# Protoboard.net
KiCad netlist of a schematic drawn in EAGLE
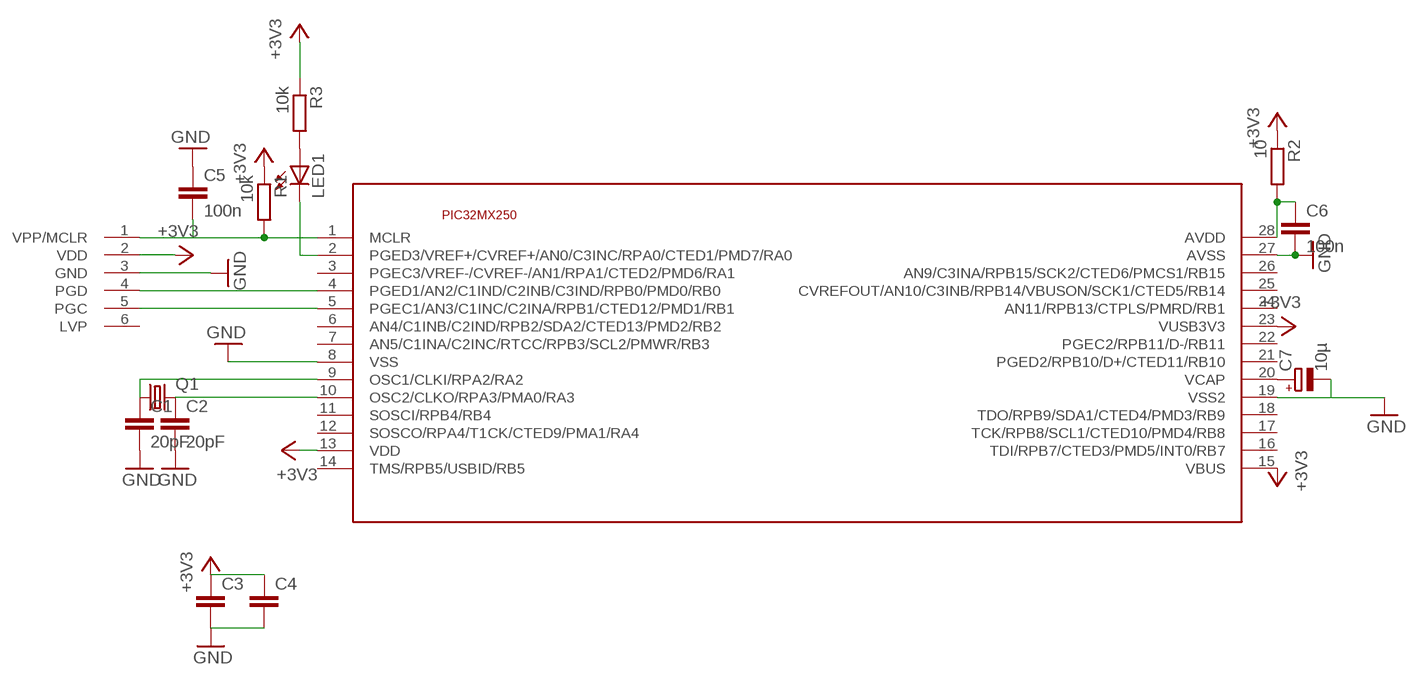
[diagram p0: schematic, sheet 1]

(export (version "E")
  (design (tool "Eeschema 10.0.6"))
  (components
    (comp (ref "C1")
      (value "20pF")
      (footprint "eagle-import:C050-024X044")
      (libsource (lib "eagle-import") (part "C-EU050-024X044"))
    )
    (comp (ref "C2")
      (value "20pF")
      (footprint "eagle-import:C050-024X044")
      (libsource (lib "eagle-import") (part "C-EU050-024X044"))
    )
    (comp (ref "C3")
      (value "C-EU050-024X044")
      (footprint "eagle-import:C050-024X044")
      (libsource (lib "eagle-import") (part "C-EU050-024X044"))
    )
    (comp (ref "C4")
      (value "C-EU050-024X044")
      (footprint "eagle-import:C050-024X044")
      (libsource (lib "eagle-import") (part "C-EU050-024X044"))
    )
    (comp (ref "C5")
      (value "100n")
      (footprint "eagle-import:C050-024X044")
      (libsource (lib "eagle-import") (part "C-EU050-024X044"))
    )
    (comp (ref "C6")
      (value "100n")
      (footprint "eagle-import:C050-024X044")
      (libsource (lib "eagle-import") (part "C-EU050-024X044"))
    )
    (comp (ref "C7")
      (value "10µ")
      (footprint "eagle-import:B45181B")
      (libsource (lib "eagle-import") (part "CPOL-EUB45181B"))
    )
    (comp (ref "LED1")
      (value "LED5MM")
      (footprint "eagle-import:LED5MM")
      (libsource (lib "eagle-import") (part "LED5MM"))
    )
    (comp (ref "Q1")
      (value "CRYSTALTC26V")
      (footprint "eagle-import:TC26V")
      (libsource (lib "eagle-import") (part "CRYSTALTC26V"))
    )
    (comp (ref "R1")
      (value "10k")
      (footprint "eagle-import:0207_10")
      (libsource (lib "eagle-import") (part "R-EU_0207/10"))
    )
    (comp (ref "R2")
      (value "10")
      (footprint "eagle-import:0207_10")
      (libsource (lib "eagle-import") (part "R-EU_0207/10"))
    )
    (comp (ref "R3")
      (value "10k")
      (footprint "eagle-import:0207_10")
      (libsource (lib "eagle-import") (part "R-EU_0207/10"))
    )
    (comp (ref "U$2")
      (value "ICSP-6_6P")
      (footprint "eagle-import:1X06-CLEANBIG")
      (libsource (lib "eagle-import") (part "ICSP-6_6P"))
    )
    (comp (ref "U$3")
      (value "PIC32MX2XXSOIC")
      (footprint "eagle-import:SOIC28")
      (libsource (lib "eagle-import") (part "PIC32MX2XXSOIC"))
    )
  )
  (nets
    (net (code "1") (name "+3V3") (class "Default")
      (node (ref "C3") (pin "1") (pinfunction "1_1") (pintype "passive"))
      (node (ref "C4") (pin "1") (pinfunction "1_1") (pintype "passive"))
      (node (ref "R1") (pin "1") (pinfunction "1_1") (pintype "passive"))
      (node (ref "R2") (pin "1") (pinfunction "1_1") (pintype "passive"))
      (node (ref "R3") (pin "1") (pinfunction "1_1") (pintype "passive"))
      (node (ref "U$2") (pin "2") (pinfunction "VDD_2") (pintype "bidirectional"))
      (node (ref "U$3") (pin "13") (pinfunction "VDD_13") (pintype "power_in"))
      (node (ref "U$3") (pin "15") (pinfunction "VBUS_15") (pintype "bidirectional"))
      (node (ref "U$3") (pin "23") (pinfunction "VUSB3V3_23") (pintype "bidirectional"))
    )
    (net (code "2") (name "GND") (class "Default")
      (node (ref "C1") (pin "2") (pinfunction "2_2") (pintype "passive"))
      (node (ref "C2") (pin "2") (pinfunction "2_2") (pintype "passive"))
      (node (ref "C3") (pin "2") (pinfunction "2_2") (pintype "passive"))
      (node (ref "C4") (pin "2") (pinfunction "2_2") (pintype "passive"))
      (node (ref "C5") (pin "1") (pinfunction "1_1") (pintype "passive"))
      (node (ref "C6") (pin "2") (pinfunction "2_2") (pintype "passive"))
      (node (ref "C7") (pin "-") (pinfunction "-_-") (pintype "passive"))
      (node (ref "U$2") (pin "3") (pinfunction "GND_3") (pintype "bidirectional"))
      (node (ref "U$3") (pin "19") (pinfunction "VSS2_19") (pintype "bidirectional"))
      (node (ref "U$3") (pin "27") (pinfunction "AVSS_27") (pintype "bidirectional"))
      (node (ref "U$3") (pin "8") (pinfunction "VSS_8") (pintype "power_in"))
    )
    (net (code "3") (name "Net-(LED1-C)") (class "Default")
      (node (ref "LED1") (pin "K") (pinfunction "C_K") (pintype "passive"))
      (node (ref "U$3") (pin "2") (pinfunction "PGED3/VREF+/CVREF+/AN0/C3INC/RPA0/CTED1/PMD7/RA0_2") (pintype "bidirectional"))
    )
    (net (code "4") (name "Net-(LED1-PadA)") (class "Default")
      (node (ref "LED1") (pin "A") (pinfunction "A_A") (pintype "passive"))
      (node (ref "R3") (pin "2") (pinfunction "2_2") (pintype "passive"))
    )
    (net (code "5") (name "Net-(U$2-PGC)") (class "Default")
      (node (ref "U$2") (pin "5") (pinfunction "PGC_5") (pintype "bidirectional"))
      (node (ref "U$3") (pin "5") (pinfunction "PGEC1/AN3/C1INC/C2INA/RPB1/CTED12/PMD1/RB1_5") (pintype "bidirectional"))
    )
    (net (code "6") (name "Net-(U$2-PGD)") (class "Default")
      (node (ref "U$2") (pin "4") (pinfunction "PGD_4") (pintype "bidirectional"))
      (node (ref "U$3") (pin "4") (pinfunction "PGED1/AN2/C1IND/C2INB/C3IND/RPB0/PMD0/RB0_4") (pintype "bidirectional"))
    )
    (net (code "7") (name "Net-(U$2-VPP{slash}MCLR)") (class "Default")
      (node (ref "C5") (pin "2") (pinfunction "2_2") (pintype "passive"))
      (node (ref "R1") (pin "2") (pinfunction "2_2") (pintype "passive"))
      (node (ref "U$2") (pin "1") (pinfunction "VPP/MCLR_1") (pintype "bidirectional"))
      (node (ref "U$3") (pin "1") (pinfunction "MCLR_1") (pintype "bidirectional"))
    )
    (net (code "8") (name "Net-(U$3-AVDD)") (class "Default")
      (node (ref "C6") (pin "1") (pinfunction "1_1") (pintype "passive"))
      (node (ref "R2") (pin "2") (pinfunction "2_2") (pintype "passive"))
      (node (ref "U$3") (pin "28") (pinfunction "AVDD_28") (pintype "bidirectional"))
    )
    (net (code "9") (name "Net-(U$3-OSC1{slash}CLKI{slash}RPA2{slash}RA2)") (class "Default")
      (node (ref "C1") (pin "1") (pinfunction "1_1") (pintype "passive"))
      (node (ref "Q1") (pin "1") (pinfunction "1_1") (pintype "passive"))
      (node (ref "U$3") (pin "9") (pinfunction "OSC1/CLKI/RPA2/RA2_9") (pintype "bidirectional"))
    )
    (net (code "10") (name "Net-(U$3-OSC2{slash}CLKO{slash}RPA3{slash}PMA0{slash}RA3)") (class "Default")
      (node (ref "C2") (pin "1") (pinfunction "1_1") (pintype "passive"))
      (node (ref "Q1") (pin "2") (pinfunction "2_2") (pintype "passive"))
      (node (ref "U$3") (pin "10") (pinfunction "OSC2/CLKO/RPA3/PMA0/RA3_10") (pintype "bidirectional"))
    )
    (net (code "11") (name "Net-(U$3-VCAP)") (class "Default")
      (node (ref "C7") (pin "+") (pinfunction "+_+") (pintype "passive"))
      (node (ref "U$3") (pin "20") (pinfunction "VCAP_20") (pintype "bidirectional"))
    )
    (net (code "12") (name "unconnected-(U$2-LVP-Pad6)") (class "Default")
      (node (ref "U$2") (pin "6") (pinfunction "LVP_6") (pintype "bidirectional"))
    )
    (net (code "13") (name "unconnected-(U$3-AN4{slash}C1INB{slash}C2IND{slash}RPB2{slash}SDA2{slash}CTED13{slash}PMD2{slash}RB2-Pad6)") (class "Default")
      (node (ref "U$3") (pin "6") (pinfunction "AN4/C1INB/C2IND/RPB2/SDA2/CTED13/PMD2/RB2_6") (pintype "bidirectional"))
    )
    (net (code "14") (name "unconnected-(U$3-AN5{slash}C1INA{slash}C2INC{slash}RTCC{slash}RPB3{slash}SCL2{slash}PMWR{slash}RB3-Pad7)") (class "Default")
      (node (ref "U$3") (pin "7") (pinfunction "AN5/C1INA/C2INC/RTCC/RPB3/SCL2/PMWR/RB3_7") (pintype "bidirectional"))
    )
    (net (code "15") (name "unconnected-(U$3-AN9{slash}C3INA{slash}RPB15{slash}SCK2{slash}CTED6{slash}PMCS1{slash}RB15-Pad26)") (class "Default")
      (node (ref "U$3") (pin "26") (pinfunction "AN9/C3INA/RPB15/SCK2/CTED6/PMCS1/RB15_26") (pintype "bidirectional"))
    )
    (net (code "16") (name "unconnected-(U$3-AN11{slash}RPB13{slash}CTPLS{slash}PMRD{slash}RB1-Pad24)") (class "Default")
      (node (ref "U$3") (pin "24") (pinfunction "AN11/RPB13/CTPLS/PMRD/RB1_24") (pintype "bidirectional"))
    )
    (net (code "17") (name "unconnected-(U$3-CVREFOUT{slash}AN10{slash}C3INB{slash}RPB14{slash}VBUSON{slash}SCK1{slash}CTED5{slash}RB14-Pad25)") (class "Default")
      (node (ref "U$3") (pin "25") (pinfunction "CVREFOUT/AN10/C3INB/RPB14/VBUSON/SCK1/CTED5/RB14_25") (pintype "bidirectional"))
    )
    (net (code "18") (name "unconnected-(U$3-PGEC2{slash}RPB11{slash}D-{slash}RB11-Pad22)") (class "Default")
      (node (ref "U$3") (pin "22") (pinfunction "PGEC2/RPB11/D-/RB11_22") (pintype "bidirectional"))
    )
    (net (code "19") (name "unconnected-(U$3-PGEC3{slash}VREF-{slash}CVREF-{slash}AN1{slash}RPA1{slash}CTED2{slash}PMD6{slash}RA1-Pad3)") (class "Default")
      (node (ref "U$3") (pin "3") (pinfunction "PGEC3/VREF-/CVREF-/AN1/RPA1/CTED2/PMD6/RA1_3") (pintype "bidirectional"))
    )
    (net (code "20") (name "unconnected-(U$3-PGED2{slash}RPB10{slash}D+{slash}CTED11{slash}RB10-Pad21)") (class "Default")
      (node (ref "U$3") (pin "21") (pinfunction "PGED2/RPB10/D+/CTED11/RB10_21") (pintype "bidirectional"))
    )
    (net (code "21") (name "unconnected-(U$3-SOSCI{slash}RPB4{slash}RB4-Pad11)") (class "Default")
      (node (ref "U$3") (pin "11") (pinfunction "SOSCI/RPB4/RB4_11") (pintype "bidirectional"))
    )
    (net (code "22") (name "unconnected-(U$3-SOSCO{slash}RPA4{slash}T1CK{slash}CTED9{slash}PMA1{slash}RA4-Pad12)") (class "Default")
      (node (ref "U$3") (pin "12") (pinfunction "SOSCO/RPA4/T1CK/CTED9/PMA1/RA4_12") (pintype "bidirectional"))
    )
    (net (code "23") (name "unconnected-(U$3-TCK{slash}RPB8{slash}SCL1{slash}CTED10{slash}PMD4{slash}RB8-Pad17)") (class "Default")
      (node (ref "U$3") (pin "17") (pinfunction "TCK/RPB8/SCL1/CTED10/PMD4/RB8_17") (pintype "bidirectional"))
    )
    (net (code "24") (name "unconnected-(U$3-TDI{slash}RPB7{slash}CTED3{slash}PMD5{slash}INT0{slash}RB7-Pad16)") (class "Default")
      (node (ref "U$3") (pin "16") (pinfunction "TDI/RPB7/CTED3/PMD5/INT0/RB7_16") (pintype "bidirectional"))
    )
    (net (code "25") (name "unconnected-(U$3-TDO{slash}RPB9{slash}SDA1{slash}CTED4{slash}PMD3{slash}RB9-Pad18)") (class "Default")
      (node (ref "U$3") (pin "18") (pinfunction "TDO/RPB9/SDA1/CTED4/PMD3/RB9_18") (pintype "bidirectional"))
    )
    (net (code "26") (name "unconnected-(U$3-TMS{slash}RPB5{slash}USBID{slash}RB5-Pad14)") (class "Default")
      (node (ref "U$3") (pin "14") (pinfunction "TMS/RPB5/USBID/RB5_14") (pintype "bidirectional"))
    )
  )
)
